# AX-03r.net
KiCad netlist of a schematic drawn in EAGLE
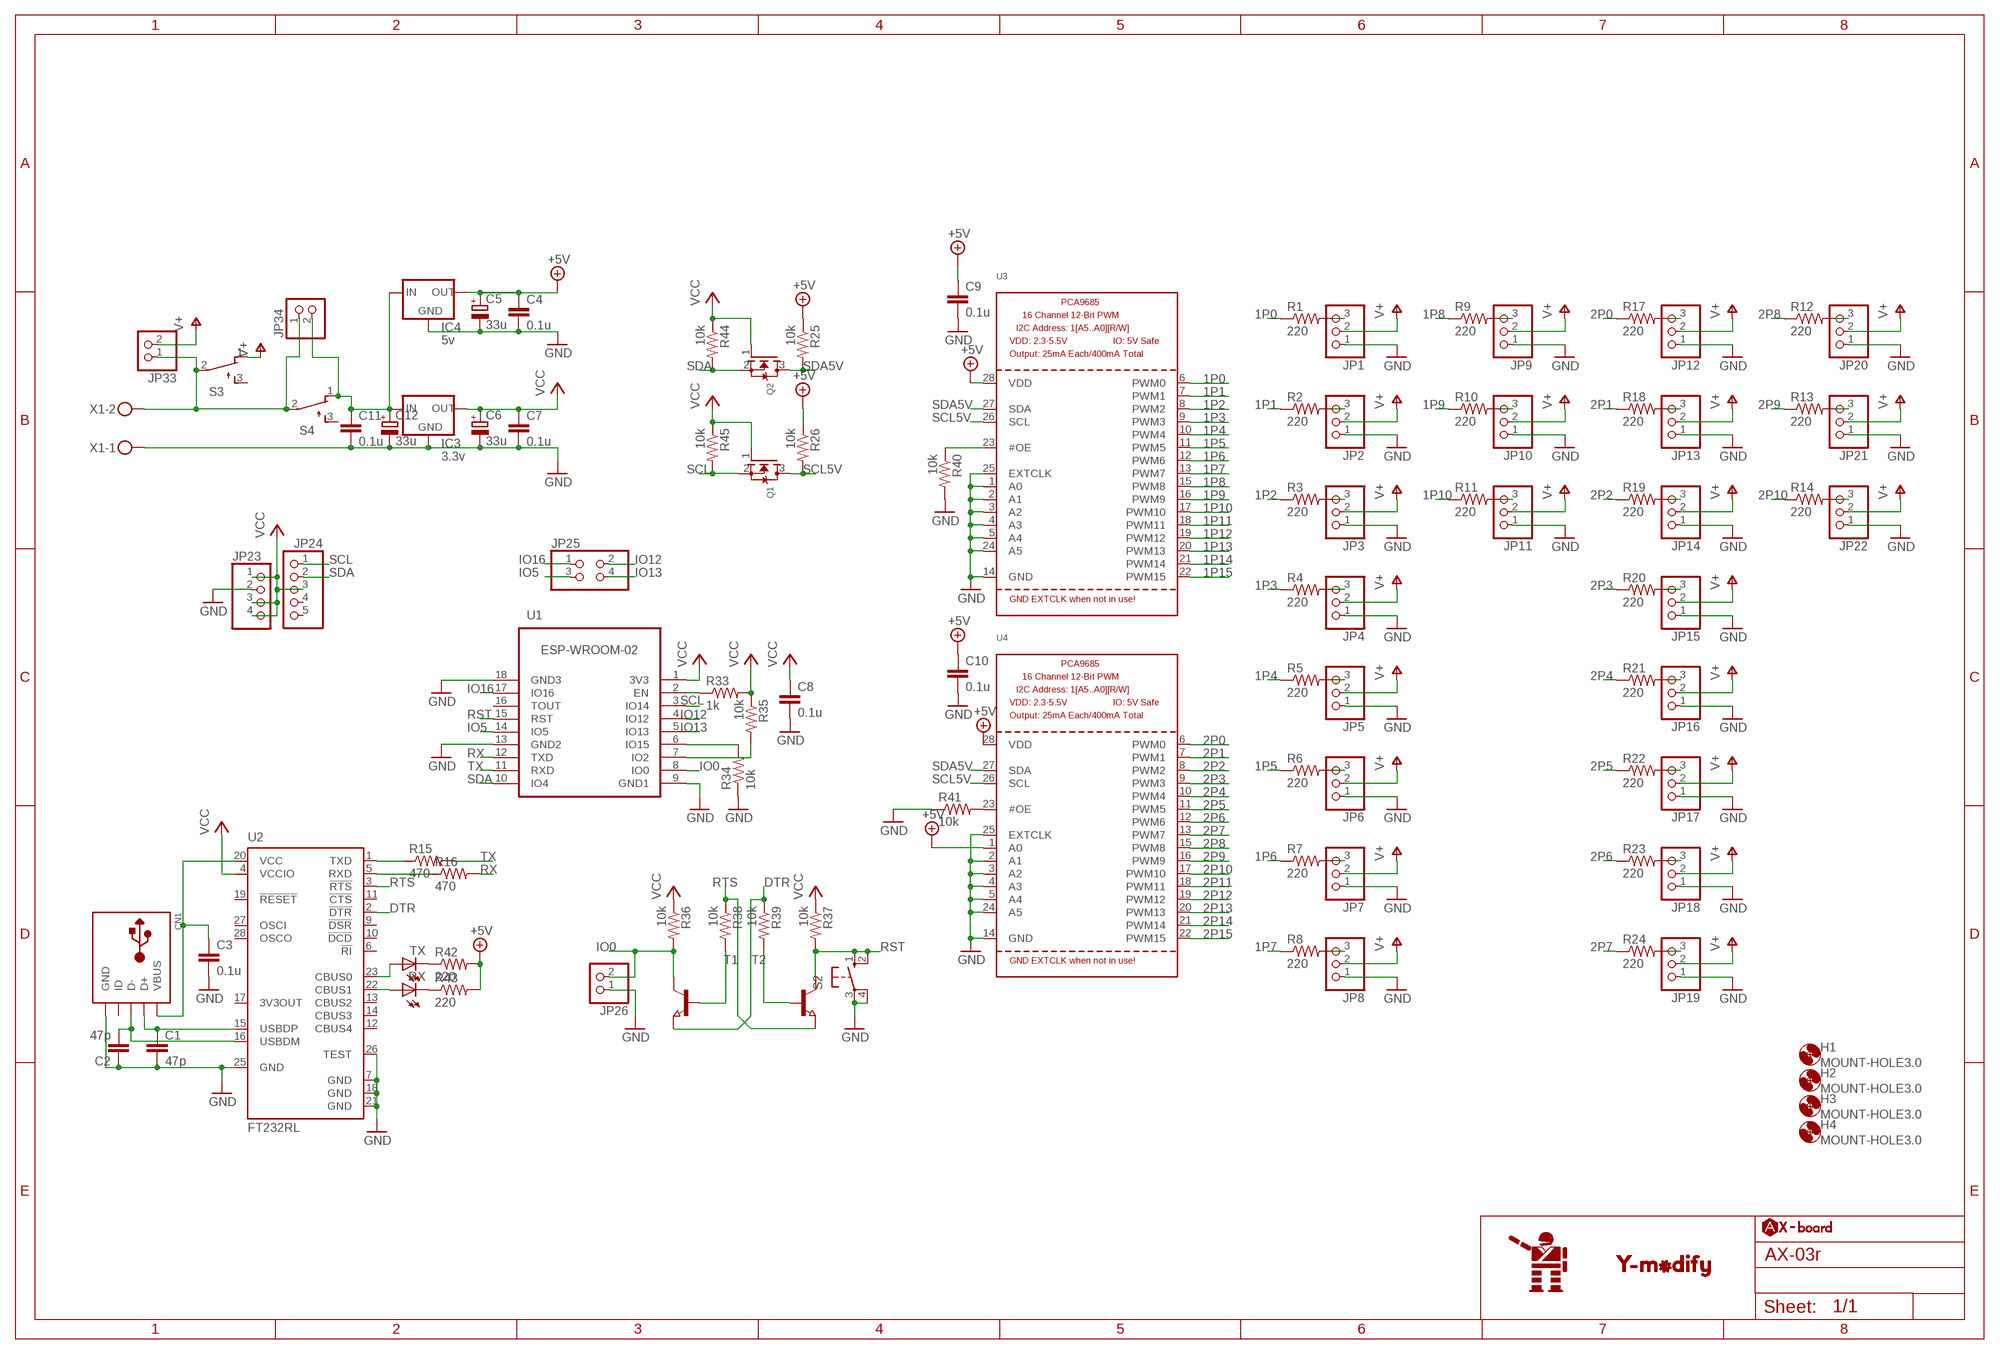
[diagram p0: schematic, sheet 1]

(export (version "E")
  (design (tool "Eeschema 10.0.6"))
  (components
    (comp (ref "C1")
      (value "47p")
      (footprint "eagle-import:C025-025X050")
      (libsource (lib "eagle-import") (part "C-EU025-025X050"))
    )
    (comp (ref "C2")
      (value "47p")
      (footprint "eagle-import:C025-025X050")
      (libsource (lib "eagle-import") (part "C-EU025-025X050"))
    )
    (comp (ref "C3")
      (value "0.1u")
      (footprint "eagle-import:C025-025X050")
      (libsource (lib "eagle-import") (part "C-EU025-025X050"))
    )
    (comp (ref "C4")
      (value "0.1u")
      (footprint "eagle-import:C025-025X050")
      (libsource (lib "eagle-import") (part "C-EU025-025X050"))
    )
    (comp (ref "C5")
      (value "33u")
      (footprint "eagle-import:E2,5-6E")
      (libsource (lib "eagle-import") (part "CPOL-EUE2,5-6E"))
    )
    (comp (ref "C6")
      (value "33u")
      (footprint "eagle-import:E2,5-6E")
      (libsource (lib "eagle-import") (part "CPOL-EUE2,5-6E"))
    )
    (comp (ref "C7")
      (value "0.1u")
      (footprint "eagle-import:C025-025X050")
      (libsource (lib "eagle-import") (part "C-EU025-025X050"))
    )
    (comp (ref "C8")
      (value "0.1u")
      (footprint "eagle-import:C025-025X050")
      (libsource (lib "eagle-import") (part "C-EU025-025X050"))
    )
    (comp (ref "C9")
      (value "0.1u")
      (footprint "eagle-import:C025-025X050")
      (libsource (lib "eagle-import") (part "C-EU025-025X050"))
    )
    (comp (ref "C10")
      (value "0.1u")
      (footprint "eagle-import:C025-025X050")
      (libsource (lib "eagle-import") (part "C-EU025-025X050"))
    )
    (comp (ref "C11")
      (value "0.1u")
      (footprint "eagle-import:C025-025X050")
      (libsource (lib "eagle-import") (part "C-EU025-025X050"))
    )
    (comp (ref "C12")
      (value "33u")
      (footprint "eagle-import:E2,5-6E")
      (libsource (lib "eagle-import") (part "CPOL-EUE2,5-6E"))
    )
    (comp (ref "CN1")
      (value "USBTHM")
      (footprint "eagle-import:USB-MINIB-THM")
      (libsource (lib "eagle-import") (part "USBTHM"))
    )
    (comp (ref "H1")
      (value "MOUNT-HOLE3.0")
      (footprint "eagle-import:3,0")
      (libsource (lib "eagle-import") (part "MOUNT-HOLE3.0"))
    )
    (comp (ref "H2")
      (value "MOUNT-HOLE3.0")
      (footprint "eagle-import:3,0")
      (libsource (lib "eagle-import") (part "MOUNT-HOLE3.0"))
    )
    (comp (ref "H3")
      (value "MOUNT-HOLE3.0")
      (footprint "eagle-import:3,0")
      (libsource (lib "eagle-import") (part "MOUNT-HOLE3.0"))
    )
    (comp (ref "H4")
      (value "MOUNT-HOLE3.0")
      (footprint "eagle-import:3,0")
      (libsource (lib "eagle-import") (part "MOUNT-HOLE3.0"))
    )
    (comp (ref "IC3")
      (value "3.3v")
      (footprint "eagle-import:78XXS")
      (libsource (lib "eagle-import") (part "78XXS"))
    )
    (comp (ref "IC4")
      (value "5v")
      (footprint "eagle-import:78XXS")
      (libsource (lib "eagle-import") (part "78XXS"))
    )
    (comp (ref "JP1")
      (value "PINHD-1X3")
      (footprint "eagle-import:1X03")
      (libsource (lib "eagle-import") (part "PINHD-1X3"))
    )
    (comp (ref "JP2")
      (value "PINHD-1X3")
      (footprint "eagle-import:1X03")
      (libsource (lib "eagle-import") (part "PINHD-1X3"))
    )
    (comp (ref "JP3")
      (value "PINHD-1X3")
      (footprint "eagle-import:1X03")
      (libsource (lib "eagle-import") (part "PINHD-1X3"))
    )
    (comp (ref "JP4")
      (value "PINHD-1X3")
      (footprint "eagle-import:1X03")
      (libsource (lib "eagle-import") (part "PINHD-1X3"))
    )
    (comp (ref "JP5")
      (value "PINHD-1X3")
      (footprint "eagle-import:1X03")
      (libsource (lib "eagle-import") (part "PINHD-1X3"))
    )
    (comp (ref "JP6")
      (value "PINHD-1X3")
      (footprint "eagle-import:1X03")
      (libsource (lib "eagle-import") (part "PINHD-1X3"))
    )
    (comp (ref "JP7")
      (value "PINHD-1X3")
      (footprint "eagle-import:1X03")
      (libsource (lib "eagle-import") (part "PINHD-1X3"))
    )
    (comp (ref "JP8")
      (value "PINHD-1X3")
      (footprint "eagle-import:1X03")
      (libsource (lib "eagle-import") (part "PINHD-1X3"))
    )
    (comp (ref "JP9")
      (value "PINHD-1X3")
      (footprint "eagle-import:1X03")
      (libsource (lib "eagle-import") (part "PINHD-1X3"))
    )
    (comp (ref "JP10")
      (value "PINHD-1X3")
      (footprint "eagle-import:1X03")
      (libsource (lib "eagle-import") (part "PINHD-1X3"))
    )
    (comp (ref "JP11")
      (value "PINHD-1X3")
      (footprint "eagle-import:1X03")
      (libsource (lib "eagle-import") (part "PINHD-1X3"))
    )
    (comp (ref "JP12")
      (value "PINHD-1X3")
      (footprint "eagle-import:1X03")
      (libsource (lib "eagle-import") (part "PINHD-1X3"))
    )
    (comp (ref "JP13")
      (value "PINHD-1X3")
      (footprint "eagle-import:1X03")
      (libsource (lib "eagle-import") (part "PINHD-1X3"))
    )
    (comp (ref "JP14")
      (value "PINHD-1X3")
      (footprint "eagle-import:1X03")
      (libsource (lib "eagle-import") (part "PINHD-1X3"))
    )
    (comp (ref "JP15")
      (value "PINHD-1X3")
      (footprint "eagle-import:1X03")
      (libsource (lib "eagle-import") (part "PINHD-1X3"))
    )
    (comp (ref "JP16")
      (value "PINHD-1X3")
      (footprint "eagle-import:1X03")
      (libsource (lib "eagle-import") (part "PINHD-1X3"))
    )
    (comp (ref "JP17")
      (value "PINHD-1X3")
      (footprint "eagle-import:1X03")
      (libsource (lib "eagle-import") (part "PINHD-1X3"))
    )
    (comp (ref "JP18")
      (value "PINHD-1X3")
      (footprint "eagle-import:1X03")
      (libsource (lib "eagle-import") (part "PINHD-1X3"))
    )
    (comp (ref "JP19")
      (value "PINHD-1X3")
      (footprint "eagle-import:1X03")
      (libsource (lib "eagle-import") (part "PINHD-1X3"))
    )
    (comp (ref "JP20")
      (value "PINHD-1X3")
      (footprint "eagle-import:1X03")
      (libsource (lib "eagle-import") (part "PINHD-1X3"))
    )
    (comp (ref "JP21")
      (value "PINHD-1X3")
      (footprint "eagle-import:1X03")
      (libsource (lib "eagle-import") (part "PINHD-1X3"))
    )
    (comp (ref "JP22")
      (value "PINHD-1X3")
      (footprint "eagle-import:1X03")
      (libsource (lib "eagle-import") (part "PINHD-1X3"))
    )
    (comp (ref "JP23")
      (value "PINHD-1X4")
      (footprint "eagle-import:1X04")
      (libsource (lib "eagle-import") (part "PINHD-1X4"))
    )
    (comp (ref "JP24")
      (value "PINHD-1X5")
      (footprint "eagle-import:1X05")
      (libsource (lib "eagle-import") (part "PINHD-1X5"))
    )
    (comp (ref "JP25")
      (value "PINHD-2X2")
      (footprint "eagle-import:2X02")
      (libsource (lib "eagle-import") (part "PINHD-2X2"))
    )
    (comp (ref "JP26")
      (value "PINHD-1X2")
      (footprint "eagle-import:1X02")
      (libsource (lib "eagle-import") (part "PINHD-1X2"))
    )
    (comp (ref "JP33")
      (value "PINHD-1X2")
      (footprint "eagle-import:1X02")
      (libsource (lib "eagle-import") (part "PINHD-1X2"))
    )
    (comp (ref "JP34")
      (value "PINHD-1X2")
      (footprint "eagle-import:1X02")
      (libsource (lib "eagle-import") (part "PINHD-1X2"))
    )
    (comp (ref "M1")
      (value "MON")
      (footprint "eagle-import:MON")
      (libsource (lib "eagle-import") (part "MON"))
    )
    (comp (ref "M2")
      (value "Y-MODIFY")
      (footprint "eagle-import:Y-MODIFY")
      (libsource (lib "eagle-import") (part "Y-MODIFY"))
    )
    (comp (ref "M3")
      (value "AXBOARD")
      (footprint "eagle-import:AXBOARD")
      (libsource (lib "eagle-import") (part "AXBOARD"))
    )
    (comp (ref "Q1")
      (value "MOSFET-NWAVE")
      (footprint "eagle-import:SOT23-W")
      (libsource (lib "eagle-import") (part "MOSFET-NWAVE"))
    )
    (comp (ref "Q2")
      (value "MOSFET-NWAVE")
      (footprint "eagle-import:SOT23-W")
      (libsource (lib "eagle-import") (part "MOSFET-NWAVE"))
    )
    (comp (ref "R1")
      (value "220")
      (footprint "eagle-import:0204V")
      (libsource (lib "eagle-import") (part "R-US_0204/2V"))
    )
    (comp (ref "R2")
      (value "220")
      (footprint "eagle-import:0204V")
      (libsource (lib "eagle-import") (part "R-US_0204/2V"))
    )
    (comp (ref "R3")
      (value "220")
      (footprint "eagle-import:0204V")
      (libsource (lib "eagle-import") (part "R-US_0204/2V"))
    )
    (comp (ref "R4")
      (value "220")
      (footprint "eagle-import:0204V")
      (libsource (lib "eagle-import") (part "R-US_0204/2V"))
    )
    (comp (ref "R5")
      (value "220")
      (footprint "eagle-import:0204V")
      (libsource (lib "eagle-import") (part "R-US_0204/2V"))
    )
    (comp (ref "R6")
      (value "220")
      (footprint "eagle-import:0204V")
      (libsource (lib "eagle-import") (part "R-US_0204/2V"))
    )
    (comp (ref "R7")
      (value "220")
      (footprint "eagle-import:0204V")
      (libsource (lib "eagle-import") (part "R-US_0204/2V"))
    )
    (comp (ref "R8")
      (value "220")
      (footprint "eagle-import:0204V")
      (libsource (lib "eagle-import") (part "R-US_0204/2V"))
    )
    (comp (ref "R9")
      (value "220")
      (footprint "eagle-import:0204V")
      (libsource (lib "eagle-import") (part "R-US_0204/2V"))
    )
    (comp (ref "R10")
      (value "220")
      (footprint "eagle-import:0204V")
      (libsource (lib "eagle-import") (part "R-US_0204/2V"))
    )
    (comp (ref "R11")
      (value "220")
      (footprint "eagle-import:0204V")
      (libsource (lib "eagle-import") (part "R-US_0204/2V"))
    )
    (comp (ref "R12")
      (value "220")
      (footprint "eagle-import:0204V")
      (libsource (lib "eagle-import") (part "R-US_0204/2V"))
    )
    (comp (ref "R13")
      (value "220")
      (footprint "eagle-import:0204V")
      (libsource (lib "eagle-import") (part "R-US_0204/2V"))
    )
    (comp (ref "R14")
      (value "220")
      (footprint "eagle-import:0204V")
      (libsource (lib "eagle-import") (part "R-US_0204/2V"))
    )
    (comp (ref "R15")
      (value "470")
      (footprint "eagle-import:0204V")
      (libsource (lib "eagle-import") (part "R-US_0204/2V"))
    )
    (comp (ref "R16")
      (value "470")
      (footprint "eagle-import:0204V")
      (libsource (lib "eagle-import") (part "R-US_0204/2V"))
    )
    (comp (ref "R17")
      (value "220")
      (footprint "eagle-import:0204V")
      (libsource (lib "eagle-import") (part "R-US_0204/2V"))
    )
    (comp (ref "R18")
      (value "220")
      (footprint "eagle-import:0204V")
      (libsource (lib "eagle-import") (part "R-US_0204/2V"))
    )
    (comp (ref "R19")
      (value "220")
      (footprint "eagle-import:0204V")
      (libsource (lib "eagle-import") (part "R-US_0204/2V"))
    )
    (comp (ref "R20")
      (value "220")
      (footprint "eagle-import:0204V")
      (libsource (lib "eagle-import") (part "R-US_0204/2V"))
    )
    (comp (ref "R21")
      (value "220")
      (footprint "eagle-import:0204V")
      (libsource (lib "eagle-import") (part "R-US_0204/2V"))
    )
    (comp (ref "R22")
      (value "220")
      (footprint "eagle-import:0204V")
      (libsource (lib "eagle-import") (part "R-US_0204/2V"))
    )
    (comp (ref "R23")
      (value "220")
      (footprint "eagle-import:0204V")
      (libsource (lib "eagle-import") (part "R-US_0204/2V"))
    )
    (comp (ref "R24")
      (value "220")
      (footprint "eagle-import:0204V")
      (libsource (lib "eagle-import") (part "R-US_0204/2V"))
    )
    (comp (ref "R25")
      (value "10k")
      (footprint "eagle-import:0204V")
      (libsource (lib "eagle-import") (part "R-US_0204/2V"))
    )
    (comp (ref "R26")
      (value "10k")
      (footprint "eagle-import:0204V")
      (libsource (lib "eagle-import") (part "R-US_0204/2V"))
    )
    (comp (ref "R33")
      (value "1k")
      (footprint "eagle-import:0204V")
      (libsource (lib "eagle-import") (part "R-US_0204/2V"))
    )
    (comp (ref "R34")
      (value "10k")
      (footprint "eagle-import:0204V")
      (libsource (lib "eagle-import") (part "R-US_0204/2V"))
    )
    (comp (ref "R35")
      (value "10k")
      (footprint "eagle-import:0204V")
      (libsource (lib "eagle-import") (part "R-US_0204/2V"))
    )
    (comp (ref "R36")
      (value "10k")
      (footprint "eagle-import:0204V")
      (libsource (lib "eagle-import") (part "R-US_0204/2V"))
    )
    (comp (ref "R37")
      (value "10k")
      (footprint "eagle-import:0204V")
      (libsource (lib "eagle-import") (part "R-US_0204/2V"))
    )
    (comp (ref "R38")
      (value "10k")
      (footprint "eagle-import:0204V")
      (libsource (lib "eagle-import") (part "R-US_0204/2V"))
    )
    (comp (ref "R39")
      (value "10k")
      (footprint "eagle-import:0204V")
      (libsource (lib "eagle-import") (part "R-US_0204/2V"))
    )
    (comp (ref "R40")
      (value "10k")
      (footprint "eagle-import:0204V")
      (libsource (lib "eagle-import") (part "R-US_0204/2V"))
    )
    (comp (ref "R41")
      (value "10k")
      (footprint "eagle-import:0204V")
      (libsource (lib "eagle-import") (part "R-US_0204/2V"))
    )
    (comp (ref "R42")
      (value "220")
      (footprint "eagle-import:0204V")
      (libsource (lib "eagle-import") (part "R-US_0204/2V"))
    )
    (comp (ref "R43")
      (value "220")
      (footprint "eagle-import:0204V")
      (libsource (lib "eagle-import") (part "R-US_0204/2V"))
    )
    (comp (ref "R44")
      (value "10k")
      (footprint "eagle-import:0204V")
      (libsource (lib "eagle-import") (part "R-US_0204/2V"))
    )
    (comp (ref "R45")
      (value "10k")
      (footprint "eagle-import:0204V")
      (libsource (lib "eagle-import") (part "R-US_0204/2V"))
    )
    (comp (ref "RX")
      (value "LED3MM")
      (footprint "eagle-import:LED3MM")
      (libsource (lib "eagle-import") (part "LED3MM"))
    )
    (comp (ref "S2")
      (value "10-XX")
      (footprint "eagle-import:B3F-10XX")
      (fields (field (name "MPN") "B3F-1000"))
      (libsource (lib "eagle-import") (part "10-XX"))
    )
    (comp (ref "S3")
      (value "TL32PO")
      (footprint "eagle-import:TL3XPO")
      (libsource (lib "eagle-import") (part "TL32PO"))
    )
    (comp (ref "S4")
      (value "TL32PO")
      (footprint "eagle-import:TL3XPO")
      (libsource (lib "eagle-import") (part "TL32PO"))
    )
    (comp (ref "T1")
      (value "NPN-TRANSISTOR_SOT23")
      (footprint "eagle-import:SOT23")
      (libsource (lib "eagle-import") (part "NPN-TRANSISTOR_SOT23"))
    )
    (comp (ref "T2")
      (value "NPN-TRANSISTOR_SOT23")
      (footprint "eagle-import:SOT23")
      (libsource (lib "eagle-import") (part "NPN-TRANSISTOR_SOT23"))
    )
    (comp (ref "TX")
      (value "LED3MM")
      (footprint "eagle-import:LED3MM")
      (libsource (lib "eagle-import") (part "LED3MM"))
    )
    (comp (ref "U1")
      (value "ESP-WROOM-02")
      (footprint "eagle-import:FRONT-FACE")
      (libsource (lib "eagle-import") (part "ESP-WROOM-02FRONT-FACE"))
    )
    (comp (ref "U2")
      (value "FT232RL")
      (footprint "eagle-import:SSOP28")
      (libsource (lib "eagle-import") (part "FT232RL"))
    )
    (comp (ref "U3")
      (value "PCA9685")
      (footprint "eagle-import:TSSOP28")
      (libsource (lib "eagle-import") (part "PCA9685"))
    )
    (comp (ref "U4")
      (value "PCA9685")
      (footprint "eagle-import:TSSOP28")
      (libsource (lib "eagle-import") (part "PCA9685"))
    )
    (comp (ref "X1")
      (value "MKDSN1,5/2-5,08")
      (footprint "eagle-import:MKDSN1,5_2-5,08")
      (libsource (lib "eagle-import") (part "MKDSN1,5/2-5,08"))
    )
  )
  (nets
    (net (code "1") (name "+5V") (class "Default")
      (node (ref "C10") (pin "1") (pinfunction "1_1") (pintype "passive"))
      (node (ref "C4") (pin "1") (pinfunction "1_1") (pintype "passive"))
      (node (ref "C5") (pin "+") (pinfunction "+_+") (pintype "passive"))
      (node (ref "C9") (pin "1") (pinfunction "1_1") (pintype "passive"))
      (node (ref "IC4") (pin "OUT") (pinfunction "OUT_OUT") (pintype "passive"))
      (node (ref "R25") (pin "1") (pinfunction "1_1") (pintype "passive"))
      (node (ref "R26") (pin "1") (pinfunction "1_1") (pintype "passive"))
      (node (ref "R42") (pin "2") (pinfunction "2_2") (pintype "passive"))
      (node (ref "R43") (pin "2") (pinfunction "2_2") (pintype "passive"))
      (node (ref "U3") (pin "28") (pinfunction "VDD_28") (pintype "power_in"))
      (node (ref "U4") (pin "1") (pinfunction "A0_1") (pintype "bidirectional"))
      (node (ref "U4") (pin "28") (pinfunction "VDD_28") (pintype "power_in"))
    )
    (net (code "2") (name "/1P0") (class "Default")
      (node (ref "R1") (pin "1") (pinfunction "1_1") (pintype "passive"))
      (node (ref "U3") (pin "6") (pinfunction "PWM0_6") (pintype "output"))
    )
    (net (code "3") (name "/1P1") (class "Default")
      (node (ref "R2") (pin "1") (pinfunction "1_1") (pintype "passive"))
      (node (ref "U3") (pin "7") (pinfunction "PWM1_7") (pintype "output"))
    )
    (net (code "4") (name "/1P2") (class "Default")
      (node (ref "R3") (pin "1") (pinfunction "1_1") (pintype "passive"))
      (node (ref "U3") (pin "8") (pinfunction "PWM2_8") (pintype "output"))
    )
    (net (code "5") (name "/1P3") (class "Default")
      (node (ref "R4") (pin "1") (pinfunction "1_1") (pintype "passive"))
      (node (ref "U3") (pin "9") (pinfunction "PWM3_9") (pintype "output"))
    )
    (net (code "6") (name "/1P4") (class "Default")
      (node (ref "R5") (pin "1") (pinfunction "1_1") (pintype "passive"))
      (node (ref "U3") (pin "10") (pinfunction "PWM4_10") (pintype "output"))
    )
    (net (code "7") (name "/1P5") (class "Default")
      (node (ref "R6") (pin "1") (pinfunction "1_1") (pintype "passive"))
      (node (ref "U3") (pin "11") (pinfunction "PWM5_11") (pintype "output"))
    )
    (net (code "8") (name "/1P6") (class "Default")
      (node (ref "R7") (pin "1") (pinfunction "1_1") (pintype "passive"))
      (node (ref "U3") (pin "12") (pinfunction "PWM6_12") (pintype "output"))
    )
    (net (code "9") (name "/1P7") (class "Default")
      (node (ref "R8") (pin "1") (pinfunction "1_1") (pintype "passive"))
      (node (ref "U3") (pin "13") (pinfunction "PWM7_13") (pintype "output"))
    )
    (net (code "10") (name "/1P8") (class "Default")
      (node (ref "R9") (pin "1") (pinfunction "1_1") (pintype "passive"))
      (node (ref "U3") (pin "15") (pinfunction "PWM8_15") (pintype "output"))
    )
    (net (code "11") (name "/1P9") (class "Default")
      (node (ref "R10") (pin "1") (pinfunction "1_1") (pintype "passive"))
      (node (ref "U3") (pin "16") (pinfunction "PWM9_16") (pintype "output"))
    )
    (net (code "12") (name "/1P10") (class "Default")
      (node (ref "R11") (pin "1") (pinfunction "1_1") (pintype "passive"))
      (node (ref "U3") (pin "17") (pinfunction "PWM10_17") (pintype "output"))
    )
    (net (code "13") (name "/1P11") (class "Default")
      (node (ref "U3") (pin "18") (pinfunction "PWM11_18") (pintype "output"))
    )
    (net (code "14") (name "/1P12") (class "Default")
      (node (ref "U3") (pin "19") (pinfunction "PWM12_19") (pintype "output"))
    )
    (net (code "15") (name "/1P13") (class "Default")
      (node (ref "U3") (pin "20") (pinfunction "PWM13_20") (pintype "output"))
    )
    (net (code "16") (name "/1P14") (class "Default")
      (node (ref "U3") (pin "21") (pinfunction "PWM14_21") (pintype "output"))
    )
    (net (code "17") (name "/1P15") (class "Default")
      (node (ref "U3") (pin "22") (pinfunction "PWM15_22") (pintype "output"))
    )
    (net (code "18") (name "/2P0") (class "Default")
      (node (ref "R17") (pin "1") (pinfunction "1_1") (pintype "passive"))
      (node (ref "U4") (pin "6") (pinfunction "PWM0_6") (pintype "output"))
    )
    (net (code "19") (name "/2P1") (class "Default")
      (node (ref "R18") (pin "1") (pinfunction "1_1") (pintype "passive"))
      (node (ref "U4") (pin "7") (pinfunction "PWM1_7") (pintype "output"))
    )
    (net (code "20") (name "/2P2") (class "Default")
      (node (ref "R19") (pin "1") (pinfunction "1_1") (pintype "passive"))
      (node (ref "U4") (pin "8") (pinfunction "PWM2_8") (pintype "output"))
    )
    (net (code "21") (name "/2P3") (class "Default")
      (node (ref "R20") (pin "1") (pinfunction "1_1") (pintype "passive"))
      (node (ref "U4") (pin "9") (pinfunction "PWM3_9") (pintype "output"))
    )
    (net (code "22") (name "/2P4") (class "Default")
      (node (ref "R21") (pin "1") (pinfunction "1_1") (pintype "passive"))
      (node (ref "U4") (pin "10") (pinfunction "PWM4_10") (pintype "output"))
    )
    (net (code "23") (name "/2P5") (class "Default")
      (node (ref "R22") (pin "1") (pinfunction "1_1") (pintype "passive"))
      (node (ref "U4") (pin "11") (pinfunction "PWM5_11") (pintype "output"))
    )
    (net (code "24") (name "/2P6") (class "Default")
      (node (ref "R23") (pin "1") (pinfunction "1_1") (pintype "passive"))
      (node (ref "U4") (pin "12") (pinfunction "PWM6_12") (pintype "output"))
    )
    (net (code "25") (name "/2P7") (class "Default")
      (node (ref "R24") (pin "1") (pinfunction "1_1") (pintype "passive"))
      (node (ref "U4") (pin "13") (pinfunction "PWM7_13") (pintype "output"))
    )
    (net (code "26") (name "/2P8") (class "Default")
      (node (ref "R12") (pin "1") (pinfunction "1_1") (pintype "passive"))
      (node (ref "U4") (pin "15") (pinfunction "PWM8_15") (pintype "output"))
    )
    (net (code "27") (name "/2P9") (class "Default")
      (node (ref "R13") (pin "1") (pinfunction "1_1") (pintype "passive"))
      (node (ref "U4") (pin "16") (pinfunction "PWM9_16") (pintype "output"))
    )
    (net (code "28") (name "/2P10") (class "Default")
      (node (ref "R14") (pin "1") (pinfunction "1_1") (pintype "passive"))
      (node (ref "U4") (pin "17") (pinfunction "PWM10_17") (pintype "output"))
    )
    (net (code "29") (name "/2P11") (class "Default")
      (node (ref "U4") (pin "18") (pinfunction "PWM11_18") (pintype "output"))
    )
    (net (code "30") (name "/2P12") (class "Default")
      (node (ref "U4") (pin "19") (pinfunction "PWM12_19") (pintype "output"))
    )
    (net (code "31") (name "/2P13") (class "Default")
      (node (ref "U4") (pin "20") (pinfunction "PWM13_20") (pintype "output"))
    )
    (net (code "32") (name "/2P14") (class "Default")
      (node (ref "U4") (pin "21") (pinfunction "PWM14_21") (pintype "output"))
    )
    (net (code "33") (name "/2P15") (class "Default")
      (node (ref "U4") (pin "22") (pinfunction "PWM15_22") (pintype "output"))
    )
    (net (code "34") (name "/DTR") (class "Default")
      (node (ref "R39") (pin "1") (pinfunction "1_1") (pintype "passive"))
      (node (ref "T1") (pin "2") (pinfunction "E_2") (pintype "passive"))
      (node (ref "U2") (pin "2") (pinfunction "~{DTR}_2") (pintype "output"))
    )
    (net (code "35") (name "/IO0") (class "Default")
      (node (ref "JP26") (pin "2") (pinfunction "2_2") (pintype "passive"))
      (node (ref "R36") (pin "2") (pinfunction "2_2") (pintype "passive"))
      (node (ref "T1") (pin "3") (pinfunction "C_3") (pintype "passive"))
      (node (ref "U1") (pin "8") (pinfunction "IO0_8") (pintype "bidirectional"))
    )
    (net (code "36") (name "/IO5") (class "Default")
      (node (ref "JP25") (pin "3") (pinfunction "3_3") (pintype "passive"))
      (node (ref "U1") (pin "14") (pinfunction "IO5_14") (pintype "open_collector"))
    )
    (net (code "37") (name "/IO12") (class "Default")
      (node (ref "JP25") (pin "2") (pinfunction "2_2") (pintype "passive"))
      (node (ref "U1") (pin "4") (pinfunction "IO12_4") (pintype "bidirectional"))
    )
    (net (code "38") (name "/IO13") (class "Default")
      (node (ref "JP25") (pin "4") (pinfunction "4_4") (pintype "passive"))
      (node (ref "U1") (pin "5") (pinfunction "IO13_5") (pintype "bidirectional"))
    )
    (net (code "39") (name "/IO16") (class "Default")
      (node (ref "JP25") (pin "1") (pinfunction "1_1") (pintype "passive"))
      (node (ref "U1") (pin "17") (pinfunction "IO16_17") (pintype "bidirectional"))
    )
    (net (code "40") (name "/RST") (class "Default")
      (node (ref "R37") (pin "2") (pinfunction "2_2") (pintype "passive"))
      (node (ref "S2") (pin "1") (pinfunction "S_1") (pintype "passive"))
      (node (ref "S2") (pin "2") (pinfunction "S1_2") (pintype "passive"))
      (node (ref "T2") (pin "3") (pinfunction "C_3") (pintype "passive"))
      (node (ref "U1") (pin "15") (pinfunction "RST_15") (pintype "bidirectional"))
    )
    (net (code "41") (name "/RTS") (class "Default")
      (node (ref "R38") (pin "1") (pinfunction "1_1") (pintype "passive"))
      (node (ref "T2") (pin "2") (pinfunction "E_2") (pintype "passive"))
      (node (ref "U2") (pin "3") (pinfunction "~{RTS}_3") (pintype "output"))
    )
    (net (code "42") (name "/RX") (class "Default")
      (node (ref "R16") (pin "2") (pinfunction "2_2") (pintype "passive"))
      (node (ref "U1") (pin "12") (pinfunction "TXD_12") (pintype "bidirectional"))
    )
    (net (code "43") (name "/SCL") (class "Default")
      (node (ref "JP24") (pin "1") (pinfunction "1_1") (pintype "passive"))
      (node (ref "Q1") (pin "2") (pinfunction "S_2") (pintype "bidirectional"))
      (node (ref "R45") (pin "2") (pinfunction "2_2") (pintype "passive"))
      (node (ref "U1") (pin "3") (pinfunction "IO14_3") (pintype "bidirectional"))
    )
    (net (code "44") (name "/SCL5V") (class "Default")
      (node (ref "Q1") (pin "3") (pinfunction "D_3") (pintype "bidirectional"))
      (node (ref "R26") (pin "2") (pinfunction "2_2") (pintype "passive"))
      (node (ref "U3") (pin "26") (pinfunction "SCL_26") (pintype "bidirectional"))
      (node (ref "U4") (pin "26") (pinfunction "SCL_26") (pintype "bidirectional"))
    )
    (net (code "45") (name "/SDA") (class "Default")
      (node (ref "JP24") (pin "2") (pinfunction "2_2") (pintype "passive"))
      (node (ref "Q2") (pin "2") (pinfunction "S_2") (pintype "bidirectional"))
      (node (ref "R44") (pin "2") (pinfunction "2_2") (pintype "passive"))
      (node (ref "U1") (pin "10") (pinfunction "IO4_10") (pintype "bidirectional"))
    )
    (net (code "46") (name "/SDA5V") (class "Default")
      (node (ref "Q2") (pin "3") (pinfunction "D_3") (pintype "bidirectional"))
      (node (ref "R25") (pin "2") (pinfunction "2_2") (pintype "passive"))
      (node (ref "U3") (pin "27") (pinfunction "SDA_27") (pintype "bidirectional"))
      (node (ref "U4") (pin "27") (pinfunction "SDA_27") (pintype "bidirectional"))
    )
    (net (code "47") (name "/TX") (class "Default")
      (node (ref "R15") (pin "2") (pinfunction "2_2") (pintype "passive"))
      (node (ref "U1") (pin "11") (pinfunction "RXD_11") (pintype "bidirectional"))
    )
    (net (code "48") (name "GND") (class "Default")
      (node (ref "C1") (pin "2") (pinfunction "2_2") (pintype "passive"))
      (node (ref "C10") (pin "2") (pinfunction "2_2") (pintype "passive"))
      (node (ref "C11") (pin "2") (pinfunction "2_2") (pintype "passive"))
      (node (ref "C12") (pin "-") (pinfunction "-_-") (pintype "passive"))
      (node (ref "C2") (pin "1") (pinfunction "1_1") (pintype "passive"))
      (node (ref "C3") (pin "2") (pinfunction "2_2") (pintype "passive"))
      (node (ref "C4") (pin "2") (pinfunction "2_2") (pintype "passive"))
      (node (ref "C5") (pin "-") (pinfunction "-_-") (pintype "passive"))
      (node (ref "C6") (pin "-") (pinfunction "-_-") (pintype "passive"))
      (node (ref "C7") (pin "2") (pinfunction "2_2") (pintype "passive"))
      (node (ref "C8") (pin "2") (pinfunction "2_2") (pintype "passive"))
      (node (ref "C9") (pin "2") (pinfunction "2_2") (pintype "passive"))
      (node (ref "CN1") (pin "GND") (pinfunction "GND_GND") (pintype "power_in"))
      (node (ref "IC3") (pin "GND") (pinfunction "GND_GND") (pintype "input"))
      (node (ref "IC4") (pin "GND") (pinfunction "GND_GND") (pintype "input"))
      (node (ref "JP1") (pin "1") (pinfunction "1_1") (pintype "passive"))
      (node (ref "JP10") (pin "1") (pinfunction "1_1") (pintype "passive"))
      (node (ref "JP11") (pin "1") (pinfunction "1_1") (pintype "passive"))
      (node (ref "JP12") (pin "1") (pinfunction "1_1") (pintype "passive"))
      (node (ref "JP13") (pin "1") (pinfunction "1_1") (pintype "passive"))
      (node (ref "JP14") (pin "1") (pinfunction "1_1") (pintype "passive"))
      (node (ref "JP15") (pin "1") (pinfunction "1_1") (pintype "passive"))
      (node (ref "JP16") (pin "1") (pinfunction "1_1") (pintype "passive"))
      (node (ref "JP17") (pin "1") (pinfunction "1_1") (pintype "passive"))
      (node (ref "JP18") (pin "1") (pinfunction "1_1") (pintype "passive"))
      (node (ref "JP19") (pin "1") (pinfunction "1_1") (pintype "passive"))
      (node (ref "JP2") (pin "1") (pinfunction "1_1") (pintype "passive"))
      (node (ref "JP20") (pin "1") (pinfunction "1_1") (pintype "passive"))
      (node (ref "JP21") (pin "1") (pinfunction "1_1") (pintype "passive"))
      (node (ref "JP22") (pin "1") (pinfunction "1_1") (pintype "passive"))
      (node (ref "JP23") (pin "2") (pinfunction "2_2") (pintype "passive"))
      (node (ref "JP26") (pin "1") (pinfunction "1_1") (pintype "passive"))
      (node (ref "JP3") (pin "1") (pinfunction "1_1") (pintype "passive"))
      (node (ref "JP4") (pin "1") (pinfunction "1_1") (pintype "passive"))
      (node (ref "JP5") (pin "1") (pinfunction "1_1") (pintype "passive"))
      (node (ref "JP6") (pin "1") (pinfunction "1_1") (pintype "passive"))
      (node (ref "JP7") (pin "1") (pinfunction "1_1") (pintype "passive"))
      (node (ref "JP8") (pin "1") (pinfunction "1_1") (pintype "passive"))
      (node (ref "JP9") (pin "1") (pinfunction "1_1") (pintype "passive"))
      (node (ref "R34") (pin "1") (pinfunction "1_1") (pintype "passive"))
      (node (ref "R40") (pin "2") (pinfunction "2_2") (pintype "passive"))
      (node (ref "R41") (pin "1") (pinfunction "1_1") (pintype "passive"))
      (node (ref "S2") (pin "3") (pinfunction "P_3") (pintype "passive"))
      (node (ref "S2") (pin "4") (pinfunction "P1_4") (pintype "passive"))
      (node (ref "U1") (pin "13") (pinfunction "GND2_13") (pintype "power_in"))
      (node (ref "U1") (pin "18") (pinfunction "GND3_18") (pintype "power_in"))
      (node (ref "U1") (pin "9") (pinfunction "GND1_9") (pintype "power_in"))
      (node (ref "U2") (pin "18") (pinfunction "GND_18") (pintype "power_in"))
      (node (ref "U2") (pin "21") (pinfunction "GND_21") (pintype "power_in"))
      (node (ref "U2") (pin "25") (pinfunction "GND_25") (pintype "power_in"))
      (node (ref "U2") (pin "26") (pinfunction "TEST_26") (pintype "input"))
      (node (ref "U2") (pin "7") (pinfunction "GND_7") (pintype "power_in"))
      (node (ref "U3") (pin "1") (pinfunction "A0_1") (pintype "bidirectional"))
      (node (ref "U3") (pin "14") (pinfunction "GND_14") (pintype "power_in"))
      (node (ref "U3") (pin "2") (pinfunction "A1_2") (pintype "bidirectional"))
      (node (ref "U3") (pin "24") (pinfunction "A5_24") (pintype "bidirectional"))
      (node (ref "U3") (pin "25") (pinfunction "EXTCLK_25") (pintype "input"))
      (node (ref "U3") (pin "3") (pinfunction "A2_3") (pintype "bidirectional"))
      (node (ref "U3") (pin "4") (pinfunction "A3_4") (pintype "bidirectional"))
      (node (ref "U3") (pin "5") (pinfunction "A4_5") (pintype "bidirectional"))
      (node (ref "U4") (pin "14") (pinfunction "GND_14") (pintype "power_in"))
      (node (ref "U4") (pin "2") (pinfunction "A1_2") (pintype "bidirectional"))
      (node (ref "U4") (pin "24") (pinfunction "A5_24") (pintype "bidirectional"))
      (node (ref "U4") (pin "25") (pinfunction "EXTCLK_25") (pintype "input"))
      (node (ref "U4") (pin "3") (pinfunction "A2_3") (pintype "bidirectional"))
      (node (ref "U4") (pin "4") (pinfunction "A3_4") (pintype "bidirectional"))
      (node (ref "U4") (pin "5") (pinfunction "A4_5") (pintype "bidirectional"))
      (node (ref "X1") (pin "1") (pinfunction "KL_1") (pintype "passive"))
    )
    (net (code "49") (name "Net-(JP1-Pad3)") (class "Default")
      (node (ref "JP1") (pin "3") (pinfunction "3_3") (pintype "passive"))
      (node (ref "R1") (pin "2") (pinfunction "2_2") (pintype "passive"))
    )
    (net (code "50") (name "Net-(JP2-Pad3)") (class "Default")
      (node (ref "JP2") (pin "3") (pinfunction "3_3") (pintype "passive"))
      (node (ref "R2") (pin "2") (pinfunction "2_2") (pintype "passive"))
    )
    (net (code "51") (name "Net-(JP3-Pad3)") (class "Default")
      (node (ref "JP3") (pin "3") (pinfunction "3_3") (pintype "passive"))
      (node (ref "R3") (pin "2") (pinfunction "2_2") (pintype "passive"))
    )
    (net (code "52") (name "Net-(JP4-Pad3)") (class "Default")
      (node (ref "JP4") (pin "3") (pinfunction "3_3") (pintype "passive"))
      (node (ref "R4") (pin "2") (pinfunction "2_2") (pintype "passive"))
    )
    (net (code "53") (name "Net-(JP5-Pad3)") (class "Default")
      (node (ref "JP5") (pin "3") (pinfunction "3_3") (pintype "passive"))
      (node (ref "R5") (pin "2") (pinfunction "2_2") (pintype "passive"))
    )
    (net (code "54") (name "Net-(JP6-Pad3)") (class "Default")
      (node (ref "JP6") (pin "3") (pinfunction "3_3") (pintype "passive"))
      (node (ref "R6") (pin "2") (pinfunction "2_2") (pintype "passive"))
    )
    (net (code "55") (name "Net-(JP7-Pad3)") (class "Default")
      (node (ref "JP7") (pin "3") (pinfunction "3_3") (pintype "passive"))
      (node (ref "R7") (pin "2") (pinfunction "2_2") (pintype "passive"))
    )
    (net (code "56") (name "Net-(JP8-Pad3)") (class "Default")
      (node (ref "JP8") (pin "3") (pinfunction "3_3") (pintype "passive"))
      (node (ref "R8") (pin "2") (pinfunction "2_2") (pintype "passive"))
    )
    (net (code "57") (name "Net-(JP9-Pad3)") (class "Default")
      (node (ref "JP9") (pin "3") (pinfunction "3_3") (pintype "passive"))
      (node (ref "R9") (pin "2") (pinfunction "2_2") (pintype "passive"))
    )
    (net (code "58") (name "Net-(JP10-Pad3)") (class "Default")
      (node (ref "JP10") (pin "3") (pinfunction "3_3") (pintype "passive"))
      (node (ref "R10") (pin "2") (pinfunction "2_2") (pintype "passive"))
    )
    (net (code "59") (name "Net-(JP11-Pad3)") (class "Default")
      (node (ref "JP11") (pin "3") (pinfunction "3_3") (pintype "passive"))
      (node (ref "R11") (pin "2") (pinfunction "2_2") (pintype "passive"))
    )
    (net (code "60") (name "Net-(JP12-Pad3)") (class "Default")
      (node (ref "JP12") (pin "3") (pinfunction "3_3") (pintype "passive"))
      (node (ref "R17") (pin "2") (pinfunction "2_2") (pintype "passive"))
    )
    (net (code "61") (name "Net-(JP13-Pad3)") (class "Default")
      (node (ref "JP13") (pin "3") (pinfunction "3_3") (pintype "passive"))
      (node (ref "R18") (pin "2") (pinfunction "2_2") (pintype "passive"))
    )
    (net (code "62") (name "Net-(JP14-Pad3)") (class "Default")
      (node (ref "JP14") (pin "3") (pinfunction "3_3") (pintype "passive"))
      (node (ref "R19") (pin "2") (pinfunction "2_2") (pintype "passive"))
    )
    (net (code "63") (name "Net-(JP15-Pad3)") (class "Default")
      (node (ref "JP15") (pin "3") (pinfunction "3_3") (pintype "passive"))
      (node (ref "R20") (pin "2") (pinfunction "2_2") (pintype "passive"))
    )
    (net (code "64") (name "Net-(JP16-Pad3)") (class "Default")
      (node (ref "JP16") (pin "3") (pinfunction "3_3") (pintype "passive"))
      (node (ref "R21") (pin "2") (pinfunction "2_2") (pintype "passive"))
    )
    (net (code "65") (name "Net-(JP17-Pad3)") (class "Default")
      (node (ref "JP17") (pin "3") (pinfunction "3_3") (pintype "passive"))
      (node (ref "R22") (pin "2") (pinfunction "2_2") (pintype "passive"))
    )
    (net (code "66") (name "Net-(JP18-Pad3)") (class "Default")
      (node (ref "JP18") (pin "3") (pinfunction "3_3") (pintype "passive"))
      (node (ref "R23") (pin "2") (pinfunction "2_2") (pintype "passive"))
    )
    (net (code "67") (name "Net-(JP19-Pad3)") (class "Default")
      (node (ref "JP19") (pin "3") (pinfunction "3_3") (pintype "passive"))
      (node (ref "R24") (pin "2") (pinfunction "2_2") (pintype "passive"))
    )
    (net (code "68") (name "Net-(JP20-Pad3)") (class "Default")
      (node (ref "JP20") (pin "3") (pinfunction "3_3") (pintype "passive"))
      (node (ref "R12") (pin "2") (pinfunction "2_2") (pintype "passive"))
    )
    (net (code "69") (name "Net-(JP21-Pad3)") (class "Default")
      (node (ref "JP21") (pin "3") (pinfunction "3_3") (pintype "passive"))
      (node (ref "R13") (pin "2") (pinfunction "2_2") (pintype "passive"))
    )
    (net (code "70") (name "Net-(JP22-Pad3)") (class "Default")
      (node (ref "JP22") (pin "3") (pinfunction "3_3") (pintype "passive"))
      (node (ref "R14") (pin "2") (pinfunction "2_2") (pintype "passive"))
    )
    (net (code "71") (name "Net-(RX-C)") (class "Default")
      (node (ref "R43") (pin "1") (pinfunction "1_1") (pintype "passive"))
      (node (ref "RX") (pin "K") (pinfunction "C_K") (pintype "passive"))
    )
    (net (code "72") (name "Net-(S3-P)") (class "Default")
      (node (ref "JP33") (pin "1") (pinfunction "1_1") (pintype "passive"))
      (node (ref "JP34") (pin "1") (pinfunction "1_1") (pintype "passive"))
      (node (ref "S3") (pin "2") (pinfunction "P_2") (pintype "passive"))
      (node (ref "S4") (pin "2") (pinfunction "P_2") (pintype "passive"))
      (node (ref "X1") (pin "2") (pinfunction "KL_2") (pintype "passive"))
    )
    (net (code "73") (name "Net-(S4-O)") (class "Default")
      (node (ref "C11") (pin "1") (pinfunction "1_1") (pintype "passive"))
      (node (ref "C12") (pin "+") (pinfunction "+_+") (pintype "passive"))
      (node (ref "IC3") (pin "IN") (pinfunction "IN_IN") (pintype "input"))
      (node (ref "IC4") (pin "IN") (pinfunction "IN_IN") (pintype "input"))
      (node (ref "JP34") (pin "2") (pinfunction "2_2") (pintype "passive"))
      (node (ref "S4") (pin "1") (pinfunction "O_1") (pintype "passive"))
    )
    (net (code "74") (name "Net-(T1-B)") (class "Default")
      (node (ref "R38") (pin "2") (pinfunction "2_2") (pintype "passive"))
      (node (ref "T1") (pin "1") (pinfunction "B_1") (pintype "passive"))
    )
    (net (code "75") (name "Net-(T2-B)") (class "Default")
      (node (ref "R39") (pin "2") (pinfunction "2_2") (pintype "passive"))
      (node (ref "T2") (pin "1") (pinfunction "B_1") (pintype "passive"))
    )
    (net (code "76") (name "Net-(TX-C)") (class "Default")
      (node (ref "R42") (pin "1") (pinfunction "1_1") (pintype "passive"))
      (node (ref "TX") (pin "K") (pinfunction "C_K") (pintype "passive"))
    )
    (net (code "77") (name "Net-(U1-EN)") (class "Default")
      (node (ref "R33") (pin "1") (pinfunction "1_1") (pintype "passive"))
      (node (ref "U1") (pin "2") (pinfunction "EN_2") (pintype "bidirectional"))
    )
    (net (code "78") (name "Net-(U1-IO2)") (class "Default")
      (node (ref "R35") (pin "2") (pinfunction "2_2") (pintype "passive"))
      (node (ref "U1") (pin "7") (pinfunction "IO2_7") (pintype "bidirectional"))
    )
    (net (code "79") (name "Net-(U1-IO15)") (class "Default")
      (node (ref "R34") (pin "2") (pinfunction "2_2") (pintype "passive"))
      (node (ref "U1") (pin "6") (pinfunction "IO15_6") (pintype "bidirectional"))
    )
    (net (code "80") (name "Net-(U2-CBUS0)") (class "Default")
      (node (ref "TX") (pin "A") (pinfunction "A_A") (pintype "passive"))
      (node (ref "U2") (pin "23") (pinfunction "CBUS0_23") (pintype "bidirectional"))
    )
    (net (code "81") (name "Net-(U2-CBUS1)") (class "Default")
      (node (ref "RX") (pin "A") (pinfunction "A_A") (pintype "passive"))
      (node (ref "U2") (pin "22") (pinfunction "CBUS1_22") (pintype "bidirectional"))
    )
    (net (code "82") (name "Net-(U2-RXD)") (class "Default")
      (node (ref "R16") (pin "1") (pinfunction "1_1") (pintype "passive"))
      (node (ref "U2") (pin "5") (pinfunction "RXD_5") (pintype "input"))
    )
    (net (code "83") (name "Net-(U2-TXD)") (class "Default")
      (node (ref "R15") (pin "1") (pinfunction "1_1") (pintype "passive"))
      (node (ref "U2") (pin "1") (pinfunction "TXD_1") (pintype "output"))
    )
    (net (code "84") (name "Net-(U2-USBDM)") (class "Default")
      (node (ref "C2") (pin "2") (pinfunction "2_2") (pintype "passive"))
      (node (ref "CN1") (pin "D-") (pinfunction "D-_D-") (pintype "bidirectional"))
      (node (ref "U2") (pin "16") (pinfunction "USBDM_16") (pintype "bidirectional"))
    )
    (net (code "85") (name "Net-(U2-USBDP)") (class "Default")
      (node (ref "C1") (pin "1") (pinfunction "1_1") (pintype "passive"))
      (node (ref "CN1") (pin "D+") (pinfunction "D+_D+") (pintype "bidirectional"))
      (node (ref "U2") (pin "15") (pinfunction "USBDP_15") (pintype "bidirectional"))
    )
    (net (code "86") (name "Net-(U2-VCC)") (class "Default")
      (node (ref "C3") (pin "1") (pinfunction "1_1") (pintype "passive"))
      (node (ref "CN1") (pin "VBUS") (pinfunction "VBUS_VBUS") (pintype "power_in"))
      (node (ref "U2") (pin "20") (pinfunction "VCC_20") (pintype "power_in"))
    )
    (net (code "87") (name "Net-(U3-#OE)") (class "Default")
      (node (ref "R40") (pin "1") (pinfunction "1_1") (pintype "passive"))
      (node (ref "U3") (pin "23") (pinfunction "#OE_23") (pintype "input"))
    )
    (net (code "88") (name "Net-(U4-#OE)") (class "Default")
      (node (ref "R41") (pin "2") (pinfunction "2_2") (pintype "passive"))
      (node (ref "U4") (pin "23") (pinfunction "#OE_23") (pintype "input"))
    )
    (net (code "89") (name "V+") (class "Default")
      (node (ref "JP1") (pin "2") (pinfunction "2_2") (pintype "passive"))
      (node (ref "JP10") (pin "2") (pinfunction "2_2") (pintype "passive"))
      (node (ref "JP11") (pin "2") (pinfunction "2_2") (pintype "passive"))
      (node (ref "JP12") (pin "2") (pinfunction "2_2") (pintype "passive"))
      (node (ref "JP13") (pin "2") (pinfunction "2_2") (pintype "passive"))
      (node (ref "JP14") (pin "2") (pinfunction "2_2") (pintype "passive"))
      (node (ref "JP15") (pin "2") (pinfunction "2_2") (pintype "passive"))
      (node (ref "JP16") (pin "2") (pinfunction "2_2") (pintype "passive"))
      (node (ref "JP17") (pin "2") (pinfunction "2_2") (pintype "passive"))
      (node (ref "JP18") (pin "2") (pinfunction "2_2") (pintype "passive"))
      (node (ref "JP19") (pin "2") (pinfunction "2_2") (pintype "passive"))
      (node (ref "JP2") (pin "2") (pinfunction "2_2") (pintype "passive"))
      (node (ref "JP20") (pin "2") (pinfunction "2_2") (pintype "passive"))
      (node (ref "JP21") (pin "2") (pinfunction "2_2") (pintype "passive"))
      (node (ref "JP22") (pin "2") (pinfunction "2_2") (pintype "passive"))
      (node (ref "JP3") (pin "2") (pinfunction "2_2") (pintype "passive"))
      (node (ref "JP33") (pin "2") (pinfunction "2_2") (pintype "passive"))
      (node (ref "JP4") (pin "2") (pinfunction "2_2") (pintype "passive"))
      (node (ref "JP5") (pin "2") (pinfunction "2_2") (pintype "passive"))
      (node (ref "JP6") (pin "2") (pinfunction "2_2") (pintype "passive"))
      (node (ref "JP7") (pin "2") (pinfunction "2_2") (pintype "passive"))
      (node (ref "JP8") (pin "2") (pinfunction "2_2") (pintype "passive"))
      (node (ref "JP9") (pin "2") (pinfunction "2_2") (pintype "passive"))
      (node (ref "S3") (pin "1") (pinfunction "O_1") (pintype "passive"))
    )
    (net (code "90") (name "VCC") (class "Default")
      (node (ref "C6") (pin "+") (pinfunction "+_+") (pintype "passive"))
      (node (ref "C7") (pin "1") (pinfunction "1_1") (pintype "passive"))
      (node (ref "C8") (pin "1") (pinfunction "1_1") (pintype "passive"))
      (node (ref "IC3") (pin "OUT") (pinfunction "OUT_OUT") (pintype "passive"))
      (node (ref "JP23") (pin "1") (pinfunction "1_1") (pintype "passive"))
      (node (ref "JP23") (pin "3") (pinfunction "3_3") (pintype "passive"))
      (node (ref "JP23") (pin "4") (pinfunction "4_4") (pintype "passive"))
      (node (ref "JP24") (pin "3") (pinfunction "3_3") (pintype "passive"))
      (node (ref "Q1") (pin "1") (pinfunction "G_1") (pintype "bidirectional"))
      (node (ref "Q2") (pin "1") (pinfunction "G_1") (pintype "bidirectional"))
      (node (ref "R33") (pin "2") (pinfunction "2_2") (pintype "passive"))
      (node (ref "R35") (pin "1") (pinfunction "1_1") (pintype "passive"))
      (node (ref "R36") (pin "1") (pinfunction "1_1") (pintype "passive"))
      (node (ref "R37") (pin "1") (pinfunction "1_1") (pintype "passive"))
      (node (ref "R44") (pin "1") (pinfunction "1_1") (pintype "passive"))
      (node (ref "R45") (pin "1") (pinfunction "1_1") (pintype "passive"))
      (node (ref "U1") (pin "1") (pinfunction "3V3_1") (pintype "power_in"))
      (node (ref "U2") (pin "4") (pinfunction "VCCIO_4") (pintype "power_in"))
    )
    (net (code "91") (name "unconnected-(CN1-PadID)") (class "Default")
      (node (ref "CN1") (pin "ID") (pinfunction "ID_ID") (pintype "bidirectional"))
    )
    (net (code "92") (name "unconnected-(JP24-Pad4)") (class "Default")
      (node (ref "JP24") (pin "4") (pinfunction "4_4") (pintype "passive"))
    )
    (net (code "93") (name "unconnected-(JP24-Pad5)") (class "Default")
      (node (ref "JP24") (pin "5") (pinfunction "5_5") (pintype "passive"))
    )
    (net (code "94") (name "unconnected-(S3-S-Pad3)") (class "Default")
      (node (ref "S3") (pin "3") (pinfunction "S_3") (pintype "passive"))
    )
    (net (code "95") (name "unconnected-(S4-S-Pad3)") (class "Default")
      (node (ref "S4") (pin "3") (pinfunction "S_3") (pintype "passive"))
    )
    (net (code "96") (name "unconnected-(U1-TOUT-Pad16)") (class "Default")
      (node (ref "U1") (pin "16") (pinfunction "TOUT_16") (pintype "bidirectional"))
    )
    (net (code "97") (name "unconnected-(U2-3V3OUT-Pad17)") (class "Default")
      (node (ref "U2") (pin "17") (pinfunction "3V3OUT_17") (pintype "output"))
    )
    (net (code "98") (name "unconnected-(U2-CBUS2-Pad13)") (class "Default")
      (node (ref "U2") (pin "13") (pinfunction "CBUS2_13") (pintype "bidirectional"))
    )
    (net (code "99") (name "unconnected-(U2-CBUS3-Pad14)") (class "Default")
      (node (ref "U2") (pin "14") (pinfunction "CBUS3_14") (pintype "bidirectional"))
    )
    (net (code "100") (name "unconnected-(U2-CBUS4-Pad12)") (class "Default")
      (node (ref "U2") (pin "12") (pinfunction "CBUS4_12") (pintype "bidirectional"))
    )
    (net (code "101") (name "unconnected-(U2-OSCI-Pad27)") (class "Default")
      (node (ref "U2") (pin "27") (pinfunction "OSCI_27") (pintype "input"))
    )
    (net (code "102") (name "unconnected-(U2-OSCO-Pad28)") (class "Default")
      (node (ref "U2") (pin "28") (pinfunction "OSCO_28") (pintype "output"))
    )
    (net (code "103") (name "unconnected-(U2-~{CTS}-Pad11)") (class "Default")
      (node (ref "U2") (pin "11") (pinfunction "~{CTS}_11") (pintype "input"))
    )
    (net (code "104") (name "unconnected-(U2-~{DCD}-Pad10)") (class "Default")
      (node (ref "U2") (pin "10") (pinfunction "~{DCD}_10") (pintype "input"))
    )
    (net (code "105") (name "unconnected-(U2-~{DSR}-Pad9)") (class "Default")
      (node (ref "U2") (pin "9") (pinfunction "~{DSR}_9") (pintype "input"))
    )
    (net (code "106") (name "unconnected-(U2-~{RESET}-Pad19)") (class "Default")
      (node (ref "U2") (pin "19") (pinfunction "~{RESET}_19") (pintype "input"))
    )
    (net (code "107") (name "unconnected-(U2-~{RI}-Pad6)") (class "Default")
      (node (ref "U2") (pin "6") (pinfunction "~{RI}_6") (pintype "input"))
    )
  )
)
